# led_breakout.net
KiCad netlist of a schematic drawn in EAGLE
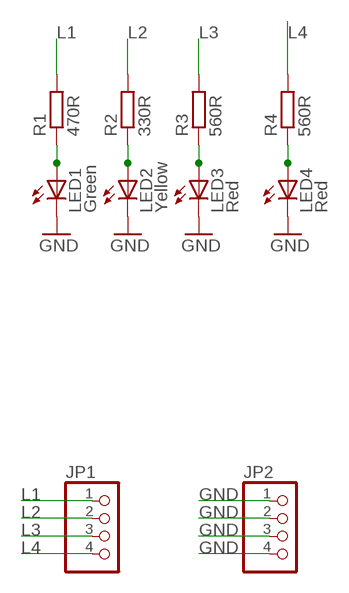
[diagram p0: schematic, sheet 1]

(export (version "E")
  (design (tool "Eeschema 10.0.6"))
  (components
    (comp (ref "JP1")
      (value "PINHD-1X4")
      (footprint "eagle-import:1X04")
      (libsource (lib "eagle-import") (part "PINHD-1X4"))
    )
    (comp (ref "JP2")
      (value "PINHD-1X4")
      (footprint "eagle-import:1X04")
      (libsource (lib "eagle-import") (part "PINHD-1X4"))
    )
    (comp (ref "LED1")
      (value "Green")
      (footprint "eagle-import:CHIPLED_1206")
      (libsource (lib "eagle-import") (part "LEDCHIPLED_1206"))
    )
    (comp (ref "LED2")
      (value "Yellow")
      (footprint "eagle-import:CHIPLED_1206")
      (libsource (lib "eagle-import") (part "LEDCHIPLED_1206"))
    )
    (comp (ref "LED3")
      (value "Red")
      (footprint "eagle-import:CHIPLED_1206")
      (libsource (lib "eagle-import") (part "LEDCHIPLED_1206"))
    )
    (comp (ref "LED4")
      (value "Red")
      (footprint "eagle-import:CHIPLED_1206")
      (libsource (lib "eagle-import") (part "LEDCHIPLED_1206"))
    )
    (comp (ref "R1")
      (value "470R")
      (footprint "eagle-import:R0805")
      (libsource (lib "eagle-import") (part "R-EU_R0805"))
    )
    (comp (ref "R2")
      (value "330R")
      (footprint "eagle-import:R0805")
      (libsource (lib "eagle-import") (part "R-EU_R0805"))
    )
    (comp (ref "R3")
      (value "560R")
      (footprint "eagle-import:R0805")
      (libsource (lib "eagle-import") (part "R-EU_R0805"))
    )
    (comp (ref "R4")
      (value "560R")
      (footprint "eagle-import:R0805")
      (libsource (lib "eagle-import") (part "R-EU_R0805"))
    )
  )
  (nets
    (net (code "1") (name "/L1") (class "Default")
      (node (ref "JP1") (pin "1") (pinfunction "1_1") (pintype "passive"))
      (node (ref "R1") (pin "2") (pinfunction "2_2") (pintype "passive"))
    )
    (net (code "2") (name "/L2") (class "Default")
      (node (ref "JP1") (pin "2") (pinfunction "2_2") (pintype "passive"))
      (node (ref "R2") (pin "2") (pinfunction "2_2") (pintype "passive"))
    )
    (net (code "3") (name "/L3") (class "Default")
      (node (ref "JP1") (pin "3") (pinfunction "3_3") (pintype "passive"))
      (node (ref "R3") (pin "2") (pinfunction "2_2") (pintype "passive"))
    )
    (net (code "4") (name "/L4") (class "Default")
      (node (ref "JP1") (pin "4") (pinfunction "4_4") (pintype "passive"))
      (node (ref "R4") (pin "2") (pinfunction "2_2") (pintype "passive"))
    )
    (net (code "5") (name "GND") (class "Default")
      (node (ref "JP2") (pin "1") (pinfunction "1_1") (pintype "passive"))
      (node (ref "JP2") (pin "2") (pinfunction "2_2") (pintype "passive"))
      (node (ref "JP2") (pin "3") (pinfunction "3_3") (pintype "passive"))
      (node (ref "JP2") (pin "4") (pinfunction "4_4") (pintype "passive"))
      (node (ref "LED1") (pin "C") (pinfunction "C_C") (pintype "passive"))
      (node (ref "LED2") (pin "C") (pinfunction "C_C") (pintype "passive"))
      (node (ref "LED3") (pin "C") (pinfunction "C_C") (pintype "passive"))
      (node (ref "LED4") (pin "C") (pinfunction "C_C") (pintype "passive"))
    )
    (net (code "6") (name "Net-(LED1-PadA)") (class "Default")
      (node (ref "LED1") (pin "A") (pinfunction "A_A") (pintype "passive"))
      (node (ref "R1") (pin "1") (pinfunction "1_1") (pintype "passive"))
    )
    (net (code "7") (name "Net-(LED2-PadA)") (class "Default")
      (node (ref "LED2") (pin "A") (pinfunction "A_A") (pintype "passive"))
      (node (ref "R2") (pin "1") (pinfunction "1_1") (pintype "passive"))
    )
    (net (code "8") (name "Net-(LED3-PadA)") (class "Default")
      (node (ref "LED3") (pin "A") (pinfunction "A_A") (pintype "passive"))
      (node (ref "R3") (pin "1") (pinfunction "1_1") (pintype "passive"))
    )
    (net (code "9") (name "Net-(LED4-PadA)") (class "Default")
      (node (ref "LED4") (pin "A") (pinfunction "A_A") (pintype "passive"))
      (node (ref "R4") (pin "1") (pinfunction "1_1") (pintype "passive"))
    )
  )
)
